# myboard.net
KiCad netlist of a schematic drawn in EAGLE
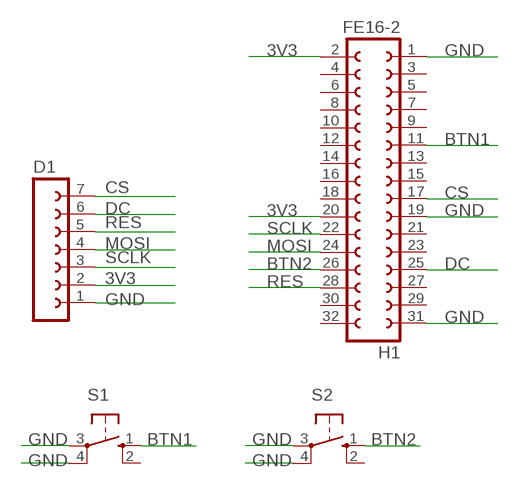
[diagram p0: schematic, sheet 1]

(export (version "E")
  (design (tool "Eeschema 10.0.6"))
  (components
    (comp (ref "D1")
      (value "FE07-1")
      (footprint "eagle-import:FE07")
      (libsource (lib "eagle-import") (part "FE07-1"))
    )
    (comp (ref "H1")
      (value "FE16-2")
      (footprint "eagle-import:FE16-2")
      (libsource (lib "eagle-import") (part "FE16-2"))
    )
    (comp (ref "S1")
      (value "40-XX")
      (footprint "eagle-import:MY-B3F-40XX")
      (libsource (lib "eagle-import") (part "40-XX"))
    )
    (comp (ref "S2")
      (value "40-XX")
      (footprint "eagle-import:MY-B3F-40XX")
      (libsource (lib "eagle-import") (part "40-XX"))
    )
  )
  (nets
    (net (code "1") (name "/3V3") (class "Default")
      (node (ref "D1") (pin "2") (pinfunction "2_2") (pintype "passive"))
      (node (ref "H1") (pin "2") (pinfunction "2_2") (pintype "passive"))
      (node (ref "H1") (pin "20") (pinfunction "20_20") (pintype "passive"))
    )
    (net (code "2") (name "/BTN1") (class "Default")
      (node (ref "H1") (pin "11") (pinfunction "11_11") (pintype "passive"))
      (node (ref "S1") (pin "1") (pinfunction "S_1") (pintype "passive"))
    )
    (net (code "3") (name "/BTN2") (class "Default")
      (node (ref "H1") (pin "26") (pinfunction "26_26") (pintype "passive"))
      (node (ref "S2") (pin "1") (pinfunction "S_1") (pintype "passive"))
    )
    (net (code "4") (name "/CS") (class "Default")
      (node (ref "D1") (pin "7") (pinfunction "7_7") (pintype "passive"))
      (node (ref "H1") (pin "17") (pinfunction "17_17") (pintype "passive"))
    )
    (net (code "5") (name "/DC") (class "Default")
      (node (ref "D1") (pin "6") (pinfunction "6_6") (pintype "passive"))
      (node (ref "H1") (pin "25") (pinfunction "25_25") (pintype "passive"))
    )
    (net (code "6") (name "/GND") (class "Default")
      (node (ref "D1") (pin "1") (pinfunction "1_1") (pintype "passive"))
      (node (ref "H1") (pin "1") (pinfunction "1_1") (pintype "passive"))
      (node (ref "H1") (pin "19") (pinfunction "19_19") (pintype "passive"))
      (node (ref "H1") (pin "31") (pinfunction "31_31") (pintype "passive"))
      (node (ref "S1") (pin "3") (pinfunction "P_3") (pintype "passive"))
      (node (ref "S1") (pin "4") (pinfunction "P1_4") (pintype "passive"))
      (node (ref "S2") (pin "3") (pinfunction "P_3") (pintype "passive"))
      (node (ref "S2") (pin "4") (pinfunction "P1_4") (pintype "passive"))
    )
    (net (code "7") (name "/MOSI") (class "Default")
      (node (ref "D1") (pin "4") (pinfunction "4_4") (pintype "passive"))
      (node (ref "H1") (pin "24") (pinfunction "24_24") (pintype "passive"))
    )
    (net (code "8") (name "/RES") (class "Default")
      (node (ref "D1") (pin "5") (pinfunction "5_5") (pintype "passive"))
      (node (ref "H1") (pin "28") (pinfunction "28_28") (pintype "passive"))
    )
    (net (code "9") (name "/SCLK") (class "Default")
      (node (ref "D1") (pin "3") (pinfunction "3_3") (pintype "passive"))
      (node (ref "H1") (pin "22") (pinfunction "22_22") (pintype "passive"))
    )
    (net (code "10") (name "unconnected-(H1-Pad3)") (class "Default")
      (node (ref "H1") (pin "3") (pinfunction "3_3") (pintype "passive"))
    )
    (net (code "11") (name "unconnected-(H1-Pad4)") (class "Default")
      (node (ref "H1") (pin "4") (pinfunction "4_4") (pintype "passive"))
    )
    (net (code "12") (name "unconnected-(H1-Pad5)") (class "Default")
      (node (ref "H1") (pin "5") (pinfunction "5_5") (pintype "passive"))
    )
    (net (code "13") (name "unconnected-(H1-Pad6)") (class "Default")
      (node (ref "H1") (pin "6") (pinfunction "6_6") (pintype "passive"))
    )
    (net (code "14") (name "unconnected-(H1-Pad7)") (class "Default")
      (node (ref "H1") (pin "7") (pinfunction "7_7") (pintype "passive"))
    )
    (net (code "15") (name "unconnected-(H1-Pad8)") (class "Default")
      (node (ref "H1") (pin "8") (pinfunction "8_8") (pintype "passive"))
    )
    (net (code "16") (name "unconnected-(H1-Pad9)") (class "Default")
      (node (ref "H1") (pin "9") (pinfunction "9_9") (pintype "passive"))
    )
    (net (code "17") (name "unconnected-(H1-Pad10)") (class "Default")
      (node (ref "H1") (pin "10") (pinfunction "10_10") (pintype "passive"))
    )
    (net (code "18") (name "unconnected-(H1-Pad12)") (class "Default")
      (node (ref "H1") (pin "12") (pinfunction "12_12") (pintype "passive"))
    )
    (net (code "19") (name "unconnected-(H1-Pad13)") (class "Default")
      (node (ref "H1") (pin "13") (pinfunction "13_13") (pintype "passive"))
    )
    (net (code "20") (name "unconnected-(H1-Pad14)") (class "Default")
      (node (ref "H1") (pin "14") (pinfunction "14_14") (pintype "passive"))
    )
    (net (code "21") (name "unconnected-(H1-Pad15)") (class "Default")
      (node (ref "H1") (pin "15") (pinfunction "15_15") (pintype "passive"))
    )
    (net (code "22") (name "unconnected-(H1-Pad16)") (class "Default")
      (node (ref "H1") (pin "16") (pinfunction "16_16") (pintype "passive"))
    )
    (net (code "23") (name "unconnected-(H1-Pad18)") (class "Default")
      (node (ref "H1") (pin "18") (pinfunction "18_18") (pintype "passive"))
    )
    (net (code "24") (name "unconnected-(H1-Pad21)") (class "Default")
      (node (ref "H1") (pin "21") (pinfunction "21_21") (pintype "passive"))
    )
    (net (code "25") (name "unconnected-(H1-Pad23)") (class "Default")
      (node (ref "H1") (pin "23") (pinfunction "23_23") (pintype "passive"))
    )
    (net (code "26") (name "unconnected-(H1-Pad27)") (class "Default")
      (node (ref "H1") (pin "27") (pinfunction "27_27") (pintype "passive"))
    )
    (net (code "27") (name "unconnected-(H1-Pad29)") (class "Default")
      (node (ref "H1") (pin "29") (pinfunction "29_29") (pintype "passive"))
    )
    (net (code "28") (name "unconnected-(H1-Pad30)") (class "Default")
      (node (ref "H1") (pin "30") (pinfunction "30_30") (pintype "passive"))
    )
    (net (code "29") (name "unconnected-(H1-Pad32)") (class "Default")
      (node (ref "H1") (pin "32") (pinfunction "32_32") (pintype "passive"))
    )
    (net (code "30") (name "unconnected-(S1-S1-Pad2)") (class "Default")
      (node (ref "S1") (pin "2") (pinfunction "S1_2") (pintype "passive"))
    )
    (net (code "31") (name "unconnected-(S2-S1-Pad2)") (class "Default")
      (node (ref "S2") (pin "2") (pinfunction "S1_2") (pintype "passive"))
    )
  )
)
